# esp32-hanover-flipdot.net
KiCad netlist of a schematic drawn in EAGLE
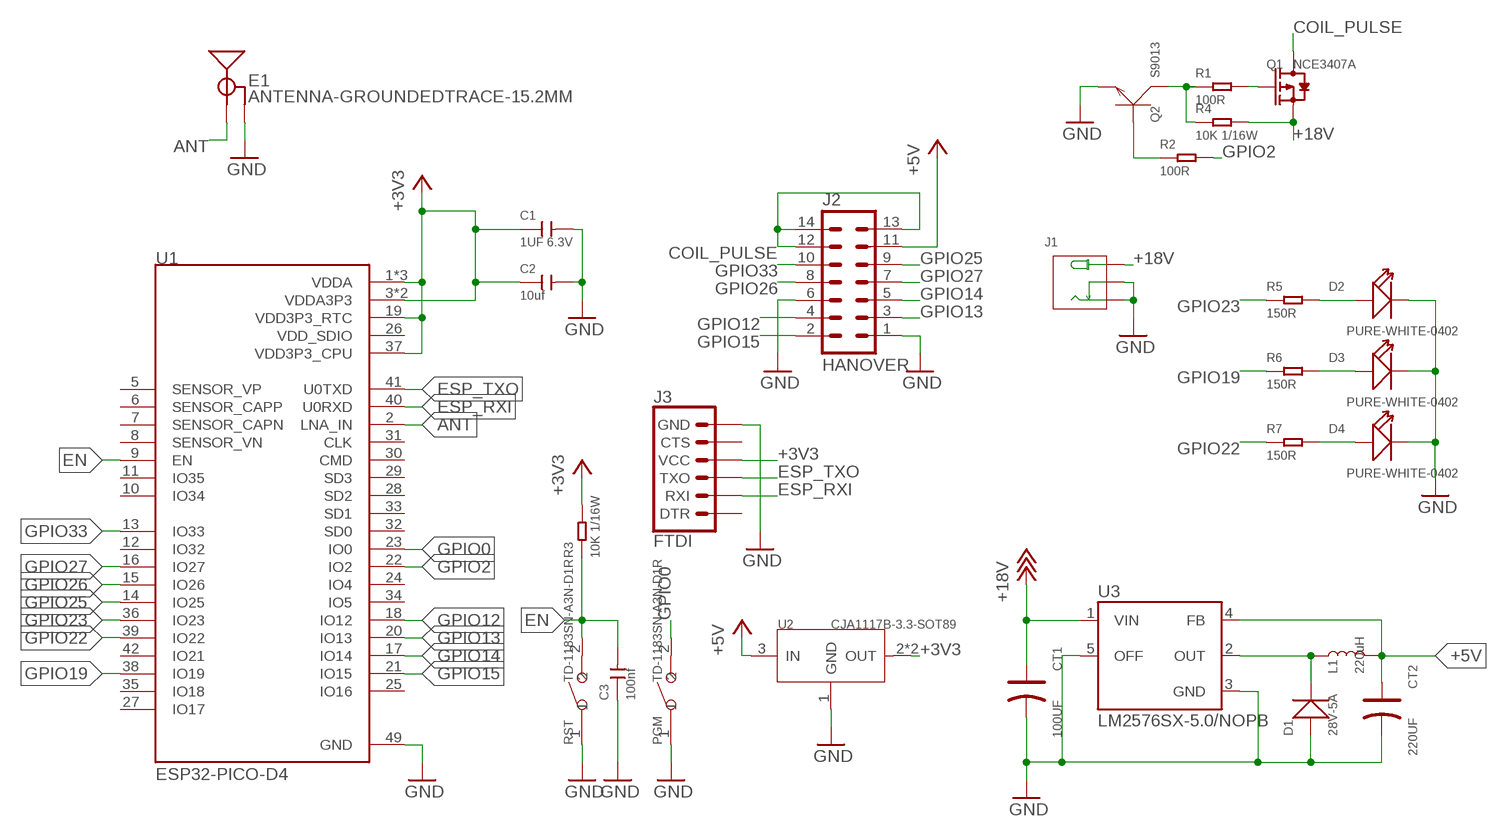
[diagram p0: schematic, sheet 1]

(export (version "E")
  (design (tool "Eeschema 10.0.6"))
  (components
    (comp (ref "C1")
      (value "1UF 6.3V")
      (footprint "eagle-import:C0402")
      (fields (field (name "MPN") "CC0402KRX5R5BB105"))
      (libsource (lib "eagle-import") (part "CERAMIC-1UF-6.3V-10%-X5R(0402)"))
    )
    (comp (ref "C2")
      (value "10uf")
      (footprint "eagle-import:C0402")
      (fields (field (name "MPN") "CC0402MRX5R5BB106"))
      (libsource (lib "eagle-import") (part "CERAMIC-10UF-6.3V-20%-X5R(0402)"))
    )
    (comp (ref "C3")
      (value "100nf")
      (footprint "eagle-import:C0402")
      (fields (field (name "MPN") "CC0402KRX7R8BB104"))
      (libsource (lib "eagle-import") (part "CERAMIC-100NF-25V-10%-X7R(0402)"))
    )
    (comp (ref "CT1")
      (value "100UF")
      (footprint "eagle-import:ELECTRO-SMD-C-6MM")
      (fields (field (name "MPN") "CS1E221M-CRE77") (field (name "MPN_1") "302030000"))
      (libsource (lib "eagle-import") (part "ALUMINUM-SMD-220UF-16V(D6.3-H7.7MM)"))
    )
    (comp (ref "CT2")
      (value "220UF")
      (footprint "eagle-import:ELECTRO-SMD-C-6MM")
      (fields (field (name "MPN") "CS1E221M-CRE77"))
      (libsource (lib "eagle-import") (part "ALUMINUM-SMD-220UF-16V(D6.3-H7.7MM)"))
    )
    (comp (ref "D1")
      (value "28V-5A")
      (footprint "eagle-import:DO-214AA")
      (fields (field (name "MPN") "SS54B"))
      (libsource (lib "eagle-import") (part "SMD-DIODE-SCHOTTKY-28V-5A(DO-214AA)"))
    )
    (comp (ref "D2")
      (value "PURE-WHITE-0402")
      (footprint "eagle-import:LED-0402")
      (fields (field (name "MPN") "16-219A/T2D-AR2T1QY/3T"))
      (libsource (lib "eagle-import") (part "SMD-LED-YELLOW-DIFFUSED-PURE-WHITE(0402)"))
    )
    (comp (ref "D3")
      (value "PURE-WHITE-0402")
      (footprint "eagle-import:LED-0402")
      (fields (field (name "MPN") "16-219A/T2D-AR2T1QY/3T"))
      (libsource (lib "eagle-import") (part "SMD-LED-YELLOW-DIFFUSED-PURE-WHITE(0402)"))
    )
    (comp (ref "D4")
      (value "PURE-WHITE-0402")
      (footprint "eagle-import:LED-0402")
      (fields (field (name "MPN") "16-219A/T2D-AR2T1QY/3T"))
      (libsource (lib "eagle-import") (part "SMD-LED-YELLOW-DIFFUSED-PURE-WHITE(0402)"))
    )
    (comp (ref "E1")
      (value "ANTENNA-GROUNDEDTRACE-15.2MM")
      (footprint "eagle-import:TRACE_ANTENNA_2.4GHZ_15.2MM")
      (libsource (lib "eagle-import") (part "ANTENNA-GROUNDEDTRACE-15.2MM"))
    )
    (comp (ref "J1")
      (value "DC-005")
      (footprint "eagle-import:3P-L14.2_W11.0_H9.0MM")
      (libsource (lib "eagle-import") (part "JACK-DC-005'DC-005'"))
    )
    (comp (ref "J2")
      (value "HANOVER")
      (footprint "eagle-import:ML14")
      (libsource (lib "eagle-import") (part "ML14"))
    )
    (comp (ref "J3")
      (value "FTDI")
      (footprint "eagle-import:6_PIN_SERIAL_TARGET_SIDE_W_SILK")
      (libsource (lib "eagle-import") (part "6_PIN_SERIAL_TARGETSILK"))
    )
    (comp (ref "L1")
      (value "220uH")
      (footprint "eagle-import:CR54")
      (libsource (lib "eagle-import") (part "INDUCTOR-CR54-3.3UH"))
    )
    (comp (ref "PGM")
      (value "TD-1183SN-A3N-D1R")
      (footprint "eagle-import:SW2-2.6-3.0X2.5X1.2+0.4MM")
      (fields (field (name "MPN") "B3U-1000P-2P-SMD"))
      (libsource (lib "eagle-import") (part "SMD-BUTTON(2P-3.0X2.5X1.2+0.4MM)-B3U-1000P-2P-SMD"))
    )
    (comp (ref "Q1")
      (value "NCE3407A")
      (footprint "eagle-import:SOT-23")
      (libsource (lib "eagle-import") (part "SMD-MOSFET-P-CH-VDC=30V-ID=4.3A-NCE3407A(SOT-23)"))
    )
    (comp (ref "Q2")
      (value "S9013")
      (footprint "eagle-import:SOT-23")
      (libsource (lib "eagle-import") (part "SMD-TRANSISTORS-NPN-25V-500MA-S9013(SOT-23)"))
    )
    (comp (ref "R1")
      (value "100R")
      (footprint "eagle-import:R0402")
      (fields (field (name "MPN") "RC0402JR-07100RL"))
      (libsource (lib "eagle-import") (part "SMD-RES-100R-5%-1/16W(0402)"))
    )
    (comp (ref "R2")
      (value "100R")
      (footprint "eagle-import:R0402")
      (fields (field (name "MPN") "RC0402JR-07100RL"))
      (libsource (lib "eagle-import") (part "SMD-RES-100R-5%-1/16W(0402)"))
    )
    (comp (ref "R3")
      (value "10K 1/16W")
      (footprint "eagle-import:R0402")
      (fields (field (name "MPN") "RC0402FR-0710KL"))
      (libsource (lib "eagle-import") (part "SMD-RES-10K-1%-1/16W(0402)"))
    )
    (comp (ref "R4")
      (value "10K 1/16W")
      (footprint "eagle-import:R0402")
      (fields (field (name "MPN") "RC0402FR-0710KL"))
      (libsource (lib "eagle-import") (part "SMD-RES-10K-1%-1/16W(0402)"))
    )
    (comp (ref "R5")
      (value "150R")
      (footprint "eagle-import:R0402")
      (fields (field (name "MPN") "RC0402JR-070RL") (field (name "MPN_1") "RC0402FR-07150RL"))
      (libsource (lib "eagle-import") (part "SMD-RES-150R-1%-1/16W(0402)"))
    )
    (comp (ref "R6")
      (value "150R")
      (footprint "eagle-import:R0402")
      (fields (field (name "MPN") "RC0402JR-070RL") (field (name "MPN_1") "RC0402FR-07150RL"))
      (libsource (lib "eagle-import") (part "SMD-RES-150R-1%-1/16W(0402)"))
    )
    (comp (ref "R7")
      (value "150R")
      (footprint "eagle-import:R0402")
      (fields (field (name "MPN") "RC0402JR-070RL") (field (name "MPN_1") "RC0402FR-07150RL"))
      (libsource (lib "eagle-import") (part "SMD-RES-150R-1%-1/16W(0402)"))
    )
    (comp (ref "RST")
      (value "TD-1183SN-A3N-D1R")
      (footprint "eagle-import:SW2-2.6-3.0X2.5X1.2+0.4MM")
      (fields (field (name "MPN") "B3U-1000P-2P-SMD"))
      (libsource (lib "eagle-import") (part "SMD-BUTTON(2P-3.0X2.5X1.2+0.4MM)-B3U-1000P-2P-SMD"))
    )
    (comp (ref "U1")
      (value "ESP32-PICO-D4")
      (footprint "eagle-import:PQFN50P700X700X104-49N")
      (fields (field (name "MF") "Espressif Systems"))
      (libsource (lib "eagle-import") (part "ESP32-PICO-D4"))
    )
    (comp (ref "U2")
      (value "CJA1117B-3.3-SOT89")
      (footprint "eagle-import:SOT-89")
      (fields (field (name "MPN") "CJA1117B-3.3"))
      (libsource (lib "eagle-import") (part "PMIC-CJA1117B-3.3(SOT-89)"))
    )
    (comp (ref "U3")
      (value "LM2576SX-5.0/NOPB")
      (footprint "eagle-import:TO263-5")
      (fields (field (name "MF") "National Semiconductor") (field (name "MP") "LM2576"))
      (libsource (lib "eagle-import") (part "LM2576S"))
    )
  )
  (nets
    (net (code "1") (name "+3V3") (class "Default")
      (node (ref "C1") (pin "1") (pinfunction "1_1") (pintype "passive"))
      (node (ref "C2") (pin "1") (pinfunction "1_1") (pintype "passive"))
      (node (ref "J3") (pin "P$4") (pinfunction "VCC_P$4") (pintype "passive"))
      (node (ref "R3") (pin "2") (pinfunction "2_2") (pintype "passive"))
      (node (ref "U1") (pin "1") (pinfunction "VDDA_1") (pintype "power_in"))
      (node (ref "U1") (pin "19") (pinfunction "VDD3P3_RTC_19") (pintype "power_in"))
      (node (ref "U1") (pin "3") (pinfunction "VDDA3P3_3") (pintype "power_in"))
      (node (ref "U1") (pin "37") (pinfunction "VDD3P3_CPU_37") (pintype "power_in"))
      (node (ref "U1") (pin "4") (pinfunction "VDDA3P3_4") (pintype "power_in"))
      (node (ref "U1") (pin "43") (pinfunction "VDDA_43") (pintype "power_in"))
      (node (ref "U1") (pin "46") (pinfunction "VDDA_46") (pintype "power_in"))
      (node (ref "U2") (pin "2") (pinfunction "OUT_2") (pintype "bidirectional"))
      (node (ref "U2") (pin "4") (pinfunction "OUT_4") (pintype "bidirectional"))
    )
    (net (code "2") (name "+5V") (class "Default")
      (node (ref "CT2") (pin "+") (pinfunction "+_+") (pintype "passive"))
      (node (ref "J2") (pin "11") (pinfunction "11_11") (pintype "passive"))
      (node (ref "L1") (pin "P$2") (pinfunction "2_P$2") (pintype "passive"))
      (node (ref "U2") (pin "3") (pinfunction "IN_3") (pintype "bidirectional"))
      (node (ref "U3") (pin "4") (pinfunction "FB_4") (pintype "input"))
    )
    (net (code "3") (name "+18V") (class "Default")
      (node (ref "CT1") (pin "+") (pinfunction "+_+") (pintype "passive"))
      (node (ref "J1") (pin "+B") (pinfunction "+_+B") (pintype "bidirectional"))
      (node (ref "J1") (pin "+T") (pinfunction "+_+T") (pintype "bidirectional"))
      (node (ref "Q1") (pin "2") (pinfunction "S_2") (pintype "passive"))
      (node (ref "R4") (pin "2") (pinfunction "2_2") (pintype "passive"))
      (node (ref "U3") (pin "1") (pinfunction "VIN_1") (pintype "power_in"))
    )
    (net (code "4") (name "/COIL_PULSE") (class "Default")
      (node (ref "J2") (pin "12") (pinfunction "12_12") (pintype "passive"))
      (node (ref "J2") (pin "13") (pinfunction "13_13") (pintype "passive"))
      (node (ref "J2") (pin "14") (pinfunction "14_14") (pintype "passive"))
      (node (ref "Q1") (pin "3") (pinfunction "D_3") (pintype "passive"))
    )
    (net (code "5") (name "/VDD_SDIO") (class "Default")
      (node (ref "U1") (pin "26") (pinfunction "VDD_SDIO_26") (pintype "power_in"))
    )
    (net (code "6") (name "ANT") (class "Default")
      (node (ref "E1") (pin "ANT") (pinfunction "SIGNAL_ANT") (pintype "bidirectional"))
      (node (ref "U1") (pin "2") (pinfunction "LNA_IN_2") (pintype "bidirectional"))
    )
    (net (code "7") (name "EN") (class "Default")
      (node (ref "C3") (pin "2") (pinfunction "2_2") (pintype "passive"))
      (node (ref "R3") (pin "1") (pinfunction "1_1") (pintype "passive"))
      (node (ref "RST") (pin "2") (pinfunction "2_2") (pintype "bidirectional"))
      (node (ref "U1") (pin "9") (pinfunction "EN_9") (pintype "input"))
    )
    (net (code "8") (name "ESP_RXI") (class "Default")
      (node (ref "J3") (pin "P$3") (pinfunction "RXI_P$3") (pintype "passive"))
      (node (ref "U1") (pin "40") (pinfunction "U0RXD_40") (pintype "bidirectional"))
    )
    (net (code "9") (name "ESP_TXO") (class "Default")
      (node (ref "J3") (pin "P$2") (pinfunction "TXO_P$2") (pintype "passive"))
      (node (ref "U1") (pin "41") (pinfunction "U0TXD_41") (pintype "bidirectional"))
    )
    (net (code "10") (name "GND") (class "Default")
      (node (ref "C1") (pin "2") (pinfunction "2_2") (pintype "passive"))
      (node (ref "C2") (pin "2") (pinfunction "2_2") (pintype "passive"))
      (node (ref "C3") (pin "1") (pinfunction "1_1") (pintype "passive"))
      (node (ref "CT1") (pin "-") (pinfunction "-_-") (pintype "passive"))
      (node (ref "CT2") (pin "-") (pinfunction "-_-") (pintype "passive"))
      (node (ref "D1") (pin "+") (pinfunction "+_+") (pintype "passive"))
      (node (ref "D2") (pin "-") (pinfunction "-_-") (pintype "passive"))
      (node (ref "D3") (pin "-") (pinfunction "-_-") (pintype "passive"))
      (node (ref "D4") (pin "-") (pinfunction "-_-") (pintype "passive"))
      (node (ref "E1") (pin "GND") (pinfunction "GND_GND") (pintype "bidirectional"))
      (node (ref "J1") (pin "-1B") (pinfunction "-_-1B") (pintype "bidirectional"))
      (node (ref "J1") (pin "-1T") (pinfunction "-_-1T") (pintype "bidirectional"))
      (node (ref "J1") (pin "-2B") (pinfunction "CDN_-2B") (pintype "bidirectional"))
      (node (ref "J1") (pin "-2T") (pinfunction "CDN_-2T") (pintype "bidirectional"))
      (node (ref "J2") (pin "1") (pinfunction "1_1") (pintype "passive"))
      (node (ref "J2") (pin "6") (pinfunction "6_6") (pintype "passive"))
      (node (ref "J3") (pin "P$6") (pinfunction "GND_P$6") (pintype "passive"))
      (node (ref "PGM") (pin "1") (pinfunction "1_1") (pintype "bidirectional"))
      (node (ref "Q2") (pin "2") (pinfunction "E_2") (pintype "passive"))
      (node (ref "RST") (pin "1") (pinfunction "1_1") (pintype "bidirectional"))
      (node (ref "U1") (pin "49") (pinfunction "GND_49") (pintype "power_in"))
      (node (ref "U2") (pin "1") (pinfunction "GND_1") (pintype "bidirectional"))
      (node (ref "U3") (pin "3") (pinfunction "GND_3") (pintype "power_in"))
      (node (ref "U3") (pin "5") (pinfunction "OFF_5") (pintype "input"))
    )
    (net (code "11") (name "GPIO0") (class "Default")
      (node (ref "PGM") (pin "2") (pinfunction "2_2") (pintype "bidirectional"))
      (node (ref "U1") (pin "23") (pinfunction "IO0_23") (pintype "bidirectional"))
    )
    (net (code "12") (name "GPIO2") (class "Default")
      (node (ref "R2") (pin "2") (pinfunction "2_2") (pintype "passive"))
      (node (ref "U1") (pin "22") (pinfunction "IO2_22") (pintype "bidirectional"))
    )
    (net (code "13") (name "GPIO12") (class "Default")
      (node (ref "J2") (pin "4") (pinfunction "4_4") (pintype "passive"))
      (node (ref "U1") (pin "18") (pinfunction "IO12_18") (pintype "bidirectional"))
    )
    (net (code "14") (name "GPIO13") (class "Default")
      (node (ref "J2") (pin "3") (pinfunction "3_3") (pintype "passive"))
      (node (ref "U1") (pin "20") (pinfunction "IO13_20") (pintype "bidirectional"))
    )
    (net (code "15") (name "GPIO14") (class "Default")
      (node (ref "J2") (pin "5") (pinfunction "5_5") (pintype "passive"))
      (node (ref "U1") (pin "17") (pinfunction "IO14_17") (pintype "bidirectional"))
    )
    (net (code "16") (name "GPIO15") (class "Default")
      (node (ref "J2") (pin "2") (pinfunction "2_2") (pintype "passive"))
      (node (ref "U1") (pin "21") (pinfunction "IO15_21") (pintype "bidirectional"))
    )
    (net (code "17") (name "GPIO19") (class "Default")
      (node (ref "R6") (pin "1") (pinfunction "1_1") (pintype "passive"))
      (node (ref "U1") (pin "38") (pinfunction "IO19_38") (pintype "bidirectional"))
    )
    (net (code "18") (name "GPIO22") (class "Default")
      (node (ref "R7") (pin "1") (pinfunction "1_1") (pintype "passive"))
      (node (ref "U1") (pin "39") (pinfunction "IO22_39") (pintype "bidirectional"))
    )
    (net (code "19") (name "GPIO23") (class "Default")
      (node (ref "R5") (pin "1") (pinfunction "1_1") (pintype "passive"))
      (node (ref "U1") (pin "36") (pinfunction "IO23_36") (pintype "bidirectional"))
    )
    (net (code "20") (name "GPIO25") (class "Default")
      (node (ref "J2") (pin "9") (pinfunction "9_9") (pintype "passive"))
      (node (ref "U1") (pin "14") (pinfunction "IO25_14") (pintype "bidirectional"))
    )
    (net (code "21") (name "GPIO26") (class "Default")
      (node (ref "J2") (pin "8") (pinfunction "8_8") (pintype "passive"))
      (node (ref "U1") (pin "15") (pinfunction "IO26_15") (pintype "bidirectional"))
    )
    (net (code "22") (name "GPIO27") (class "Default")
      (node (ref "J2") (pin "7") (pinfunction "7_7") (pintype "passive"))
      (node (ref "U1") (pin "16") (pinfunction "IO27_16") (pintype "bidirectional"))
    )
    (net (code "23") (name "GPIO33") (class "Default")
      (node (ref "J2") (pin "10") (pinfunction "10_10") (pintype "passive"))
      (node (ref "U1") (pin "13") (pinfunction "IO33_13") (pintype "bidirectional"))
    )
    (net (code "24") (name "Net-(D2-Pad+)") (class "Default")
      (node (ref "D2") (pin "+") (pinfunction "+_+") (pintype "passive"))
      (node (ref "R5") (pin "2") (pinfunction "2_2") (pintype "passive"))
    )
    (net (code "25") (name "Net-(D3-Pad+)") (class "Default")
      (node (ref "D3") (pin "+") (pinfunction "+_+") (pintype "passive"))
      (node (ref "R6") (pin "2") (pinfunction "2_2") (pintype "passive"))
    )
    (net (code "26") (name "Net-(D4-Pad+)") (class "Default")
      (node (ref "D4") (pin "+") (pinfunction "+_+") (pintype "passive"))
      (node (ref "R7") (pin "2") (pinfunction "2_2") (pintype "passive"))
    )
    (net (code "27") (name "Net-(L1-1)") (class "Default")
      (node (ref "D1") (pin "-") (pinfunction "-_-") (pintype "passive"))
      (node (ref "L1") (pin "P$1") (pinfunction "1_P$1") (pintype "passive"))
      (node (ref "U3") (pin "2") (pinfunction "OUT_2") (pintype "output"))
    )
    (net (code "28") (name "Net-(Q1-G)") (class "Default")
      (node (ref "Q1") (pin "1") (pinfunction "G_1") (pintype "passive"))
      (node (ref "R1") (pin "2") (pinfunction "2_2") (pintype "passive"))
    )
    (net (code "29") (name "Net-(Q2-B)") (class "Default")
      (node (ref "Q2") (pin "1") (pinfunction "B_1") (pintype "passive"))
      (node (ref "R2") (pin "1") (pinfunction "1_1") (pintype "passive"))
    )
    (net (code "30") (name "Net-(Q2-C)") (class "Default")
      (node (ref "Q2") (pin "3") (pinfunction "C_3") (pintype "passive"))
      (node (ref "R1") (pin "1") (pinfunction "1_1") (pintype "passive"))
      (node (ref "R4") (pin "1") (pinfunction "1_1") (pintype "passive"))
    )
    (net (code "31") (name "unconnected-(J3-CTS-PadP$5)") (class "Default")
      (node (ref "J3") (pin "P$5") (pinfunction "CTS_P$5") (pintype "passive"))
    )
    (net (code "32") (name "unconnected-(J3-DTR-PadP$1)") (class "Default")
      (node (ref "J3") (pin "P$1") (pinfunction "DTR_P$1") (pintype "passive"))
    )
    (net (code "33") (name "unconnected-(U1-CLK-Pad31)") (class "Default")
      (node (ref "U1") (pin "31") (pinfunction "CLK_31") (pintype "bidirectional"))
    )
    (net (code "34") (name "unconnected-(U1-CMD-Pad30)") (class "Default")
      (node (ref "U1") (pin "30") (pinfunction "CMD_30") (pintype "bidirectional"))
    )
    (net (code "35") (name "unconnected-(U1-IO4-Pad24)") (class "Default")
      (node (ref "U1") (pin "24") (pinfunction "IO4_24") (pintype "bidirectional"))
    )
    (net (code "36") (name "unconnected-(U1-IO5-Pad34)") (class "Default")
      (node (ref "U1") (pin "34") (pinfunction "IO5_34") (pintype "bidirectional"))
    )
    (net (code "37") (name "unconnected-(U1-IO16-Pad25)") (class "Default")
      (node (ref "U1") (pin "25") (pinfunction "IO16_25") (pintype "bidirectional"))
    )
    (net (code "38") (name "unconnected-(U1-IO17-Pad27)") (class "Default")
      (node (ref "U1") (pin "27") (pinfunction "IO17_27") (pintype "bidirectional"))
    )
    (net (code "39") (name "unconnected-(U1-IO18-Pad35)") (class "Default")
      (node (ref "U1") (pin "35") (pinfunction "IO18_35") (pintype "bidirectional"))
    )
    (net (code "40") (name "unconnected-(U1-IO21-Pad42)") (class "Default")
      (node (ref "U1") (pin "42") (pinfunction "IO21_42") (pintype "bidirectional"))
    )
    (net (code "41") (name "unconnected-(U1-IO32-Pad12)") (class "Default")
      (node (ref "U1") (pin "12") (pinfunction "IO32_12") (pintype "bidirectional"))
    )
    (net (code "42") (name "unconnected-(U1-IO34-Pad10)") (class "Default")
      (node (ref "U1") (pin "10") (pinfunction "IO34_10") (pintype "input"))
    )
    (net (code "43") (name "unconnected-(U1-IO35-Pad11)") (class "Default")
      (node (ref "U1") (pin "11") (pinfunction "IO35_11") (pintype "input"))
    )
    (net (code "44") (name "unconnected-(U1-SD0-Pad32)") (class "Default")
      (node (ref "U1") (pin "32") (pinfunction "SD0_32") (pintype "bidirectional"))
    )
    (net (code "45") (name "unconnected-(U1-SD1-Pad33)") (class "Default")
      (node (ref "U1") (pin "33") (pinfunction "SD1_33") (pintype "bidirectional"))
    )
    (net (code "46") (name "unconnected-(U1-SD2-Pad28)") (class "Default")
      (node (ref "U1") (pin "28") (pinfunction "SD2_28") (pintype "bidirectional"))
    )
    (net (code "47") (name "unconnected-(U1-SD3-Pad29)") (class "Default")
      (node (ref "U1") (pin "29") (pinfunction "SD3_29") (pintype "bidirectional"))
    )
    (net (code "48") (name "unconnected-(U1-SENSOR_CAPN-Pad7)") (class "Default")
      (node (ref "U1") (pin "7") (pinfunction "SENSOR_CAPN_7") (pintype "input"))
    )
    (net (code "49") (name "unconnected-(U1-SENSOR_CAPP-Pad6)") (class "Default")
      (node (ref "U1") (pin "6") (pinfunction "SENSOR_CAPP_6") (pintype "input"))
    )
    (net (code "50") (name "unconnected-(U1-SENSOR_VN-Pad8)") (class "Default")
      (node (ref "U1") (pin "8") (pinfunction "SENSOR_VN_8") (pintype "input"))
    )
    (net (code "51") (name "unconnected-(U1-SENSOR_VP-Pad5)") (class "Default")
      (node (ref "U1") (pin "5") (pinfunction "SENSOR_VP_5") (pintype "input"))
    )
  )
)
